# SMDBoard.net
KiCad netlist of a schematic drawn in EAGLE
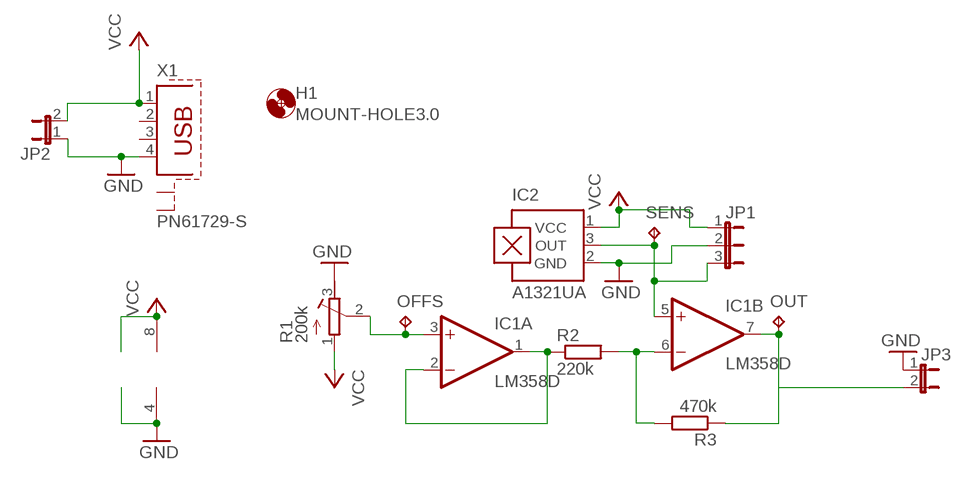
[diagram p0: schematic, sheet 1]

(export (version "E")
  (design (tool "Eeschema 10.0.6"))
  (components
    (comp (ref "H1")
      (value "MOUNT-HOLE3.0")
      (footprint "eagle-import:3,0")
      (libsource (lib "eagle-import") (part "MOUNT-HOLE3.0"))
    )
    (comp (ref "IC1")
      (value "LM358D")
      (footprint "eagle-import:SO08")
      (libsource (lib "eagle-import") (part "LM358D"))
    )
    (comp (ref "IC2")
      (value "A1321UA")
      (footprint "eagle-import:SIP3-UA")
      (fields (field (name "MF") "ALLEGRO MICROSYSTEMS, INC.") (field (name "MPN") "A1321EUA-T"))
      (libsource (lib "eagle-import") (part "A13?UA21"))
    )
    (comp (ref "JP1")
      (value "JP2E")
      (footprint "eagle-import:JP2")
      (libsource (lib "eagle-import") (part "JP2E"))
    )
    (comp (ref "JP2")
      (value "JP1E")
      (footprint "eagle-import:JP1")
      (libsource (lib "eagle-import") (part "JP1E"))
    )
    (comp (ref "JP3")
      (value "JP1E")
      (footprint "eagle-import:JP1")
      (libsource (lib "eagle-import") (part "JP1E"))
    )
    (comp (ref "OFFS")
      (value "TPB1,27")
      (footprint "eagle-import:B1,27")
      (libsource (lib "eagle-import") (part "TPB1,27"))
    )
    (comp (ref "OUT")
      (value "TPB1,27")
      (footprint "eagle-import:B1,27")
      (libsource (lib "eagle-import") (part "TPB1,27"))
    )
    (comp (ref "R1")
      (value "200k")
      (footprint "eagle-import:RTRIM3296W")
      (libsource (lib "eagle-import") (part "R-TRIMM3296W"))
    )
    (comp (ref "R2")
      (value "220k")
      (footprint "eagle-import:R0805")
      (libsource (lib "eagle-import") (part "R-EU_R0805"))
    )
    (comp (ref "R3")
      (value "470k")
      (footprint "eagle-import:R0805")
      (libsource (lib "eagle-import") (part "R-EU_R0805"))
    )
    (comp (ref "SENS")
      (value "TPB1,27")
      (footprint "eagle-import:B1,27")
      (libsource (lib "eagle-import") (part "TPB1,27"))
    )
    (comp (ref "X1")
      (value "PN61729-S")
      (footprint "eagle-import:PN61729-S")
      (libsource (lib "eagle-import") (part "PN61729-S"))
    )
  )
  (nets
    (net (code "1") (name "GND") (class "Default")
      (node (ref "IC1") (pin "4") (pinfunction "V-_4") (pintype "power_in"))
      (node (ref "IC2") (pin "2") (pinfunction "GND_2") (pintype "power_in"))
      (node (ref "JP1") (pin "2") (pinfunction "2_2") (pintype "passive"))
      (node (ref "JP2") (pin "1") (pinfunction "1_1") (pintype "passive"))
      (node (ref "JP3") (pin "1") (pinfunction "1_1") (pintype "passive"))
      (node (ref "R1") (pin "3") (pinfunction "E_3") (pintype "passive"))
      (node (ref "X1") (pin "4") (pinfunction "4_4") (pintype "passive"))
    )
    (net (code "2") (name "Net-(IC1A-+IN)") (class "Default")
      (node (ref "IC1") (pin "3") (pinfunction "+IN_3") (pintype "input"))
      (node (ref "OFFS") (pin "TP") (pinfunction "TP_TP") (pintype "input"))
      (node (ref "R1") (pin "2") (pinfunction "S_2") (pintype "passive"))
    )
    (net (code "3") (name "Net-(IC1A--IN)") (class "Default")
      (node (ref "IC1") (pin "1") (pinfunction "OUT_1") (pintype "output"))
      (node (ref "IC1") (pin "2") (pinfunction "-IN_2") (pintype "input"))
      (node (ref "R2") (pin "1") (pinfunction "1_1") (pintype "passive"))
    )
    (net (code "4") (name "Net-(IC1B-+IN)") (class "Default")
      (node (ref "IC1") (pin "5") (pinfunction "+IN_5") (pintype "input"))
      (node (ref "IC2") (pin "3") (pinfunction "OUT_3") (pintype "output"))
      (node (ref "JP1") (pin "3") (pinfunction "3_3") (pintype "passive"))
      (node (ref "SENS") (pin "TP") (pinfunction "TP_TP") (pintype "input"))
    )
    (net (code "5") (name "Net-(IC1B--IN)") (class "Default")
      (node (ref "IC1") (pin "6") (pinfunction "-IN_6") (pintype "input"))
      (node (ref "R2") (pin "2") (pinfunction "2_2") (pintype "passive"))
      (node (ref "R3") (pin "2") (pinfunction "2_2") (pintype "passive"))
    )
    (net (code "6") (name "Net-(IC1B-OUT)") (class "Default")
      (node (ref "IC1") (pin "7") (pinfunction "OUT_7") (pintype "output"))
      (node (ref "JP3") (pin "2") (pinfunction "2_2") (pintype "passive"))
      (node (ref "OUT") (pin "TP") (pinfunction "TP_TP") (pintype "input"))
      (node (ref "R3") (pin "1") (pinfunction "1_1") (pintype "passive"))
    )
    (net (code "7") (name "VCC") (class "Default")
      (node (ref "IC1") (pin "8") (pinfunction "V+_8") (pintype "power_in"))
      (node (ref "IC2") (pin "1") (pinfunction "VCC_1") (pintype "power_in"))
      (node (ref "JP1") (pin "1") (pinfunction "1_1") (pintype "passive"))
      (node (ref "JP2") (pin "2") (pinfunction "2_2") (pintype "passive"))
      (node (ref "R1") (pin "1") (pinfunction "A_1") (pintype "passive"))
      (node (ref "X1") (pin "1") (pinfunction "1_1") (pintype "passive"))
    )
    (net (code "8") (name "unconnected-(X1-Pad2)") (class "Default")
      (node (ref "X1") (pin "2") (pinfunction "2_2") (pintype "passive"))
    )
    (net (code "9") (name "unconnected-(X1-Pad3)") (class "Default")
      (node (ref "X1") (pin "3") (pinfunction "3_3") (pintype "passive"))
    )
    (net (code "10") (name "unconnected-(X1-PadS1)") (class "Default")
      (node (ref "X1") (pin "S1") (pinfunction "S1_S1") (pintype "passive"))
    )
    (net (code "11") (name "unconnected-(X1-PadS2)") (class "Default")
      (node (ref "X1") (pin "S2") (pinfunction "S2_S2") (pintype "passive"))
    )
  )
)
